# Pico_PSU.net
KiCad netlist of a schematic drawn in Altium Designer
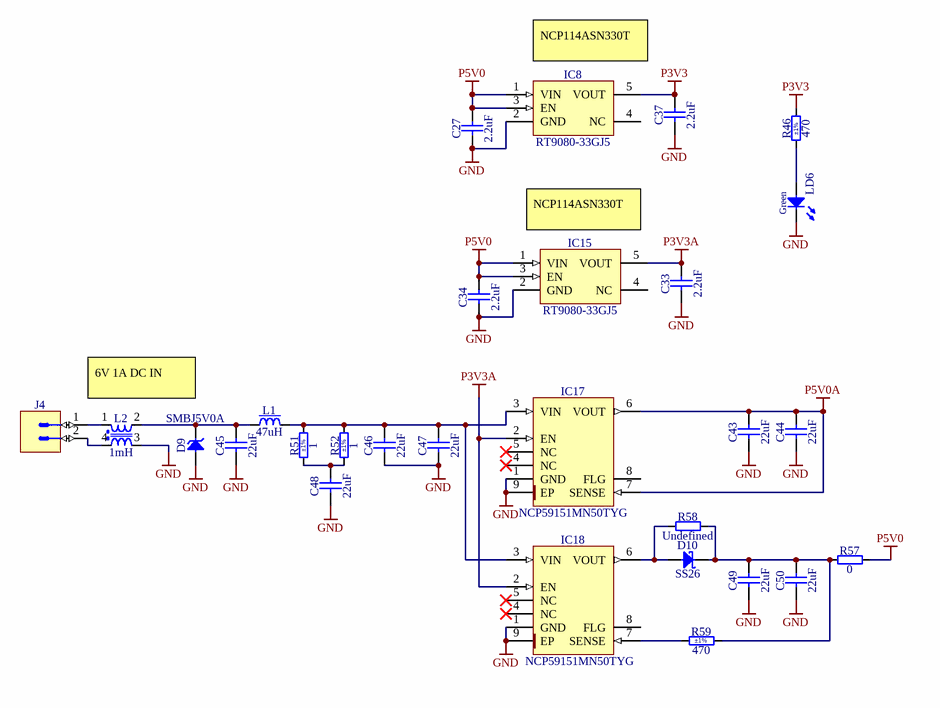
[diagram p0: Pico_PSU.SchDoc]

(export (version "E")
  (design (tool "Eeschema 10.0.6"))
  (components
    (comp (ref "C27")
      (value "2.2uF")
      (footprint "CAPC1608X90N")
      (description "Non-polarised capacitor")
      (fields
        (field (name "PART NUMBER") "CC0603_2.2UF_10V_20%_X7R")
        (field (name "VOLTAGE") "10V")
        (field (name "AUTHOR") "CERN DEM JLC")
      )
      (libsource (lib "Capacitors") (part "Capacitor - non polarized"))
    )
    (comp (ref "C33")
      (value "2.2uF")
      (footprint "CAPC1608X90N")
      (description "Non-polarised capacitor")
      (fields
        (field (name "PART NUMBER") "CC0603_2.2UF_10V_20%_X7R")
        (field (name "VOLTAGE") "10V")
        (field (name "AUTHOR") "CERN DEM JLC")
      )
      (libsource (lib "Capacitors") (part "Capacitor - non polarized"))
    )
    (comp (ref "C34")
      (value "2.2uF")
      (footprint "CAPC1608X90N")
      (description "Non-polarised capacitor")
      (fields
        (field (name "PART NUMBER") "CC0603_2.2UF_10V_20%_X7R")
        (field (name "VOLTAGE") "10V")
        (field (name "AUTHOR") "CERN DEM JLC")
      )
      (libsource (lib "Capacitors") (part "Capacitor - non polarized"))
    )
    (comp (ref "C37")
      (value "2.2uF")
      (footprint "CAPC1608X90N")
      (description "Non-polarised capacitor")
      (fields
        (field (name "PART NUMBER") "CC0603_2.2UF_10V_20%_X7R")
        (field (name "VOLTAGE") "10V")
        (field (name "AUTHOR") "CERN DEM JLC")
      )
      (libsource (lib "Capacitors") (part "Capacitor - non polarized"))
    )
    (comp (ref "C43")
      (value "22uF")
      (footprint "CAPC3216X180N")
      (description "Non-polarised capacitor")
      (fields
        (field (name "PART NUMBER") "CC1206_22UF_10V_10%_X7R")
        (field (name "VOLTAGE") "10V")
        (field (name "AUTHOR") "CERN DEM JLC")
      )
      (libsource (lib "Capacitors") (part "Capacitor - non polarized"))
    )
    (comp (ref "C44")
      (value "22uF")
      (footprint "CAPC3216X180N")
      (description "Non-polarised capacitor")
      (fields
        (field (name "PART NUMBER") "CC1206_22UF_10V_10%_X7R")
        (field (name "VOLTAGE") "10V")
        (field (name "AUTHOR") "CERN DEM JLC")
      )
      (libsource (lib "Capacitors") (part "Capacitor - non polarized"))
    )
    (comp (ref "C45")
      (value "22uF")
      (footprint "CAPC3216X180N")
      (description "Non-polarised capacitor")
      (fields
        (field (name "PART NUMBER") "CC1206_22UF_10V_10%_X7R")
        (field (name "VOLTAGE") "10V")
        (field (name "AUTHOR") "CERN DEM JLC")
      )
      (libsource (lib "Capacitors") (part "Capacitor - non polarized"))
    )
    (comp (ref "C46")
      (value "22uF")
      (footprint "CAPC3216X180N")
      (description "Non-polarised capacitor")
      (fields
        (field (name "PART NUMBER") "CC1206_22UF_10V_10%_X7R")
        (field (name "VOLTAGE") "10V")
        (field (name "AUTHOR") "CERN DEM JLC")
      )
      (libsource (lib "Capacitors") (part "Capacitor - non polarized"))
    )
    (comp (ref "C47")
      (value "22uF")
      (footprint "CAPC3216X180N")
      (description "Non-polarised capacitor")
      (fields
        (field (name "PART NUMBER") "CC1206_22UF_10V_10%_X7R")
        (field (name "VOLTAGE") "10V")
        (field (name "AUTHOR") "CERN DEM JLC")
      )
      (libsource (lib "Capacitors") (part "Capacitor - non polarized"))
    )
    (comp (ref "C48")
      (value "22uF")
      (footprint "CAPC3216X180N")
      (description "Non-polarised capacitor")
      (fields
        (field (name "PART NUMBER") "CC1206_22UF_10V_10%_X7R")
        (field (name "VOLTAGE") "10V")
        (field (name "AUTHOR") "CERN DEM JLC")
      )
      (libsource (lib "Capacitors") (part "Capacitor - non polarized"))
    )
    (comp (ref "C49")
      (value "22uF")
      (footprint "CAPC3216X180N")
      (description "Non-polarised capacitor")
      (fields
        (field (name "PART NUMBER") "CC1206_22UF_10V_10%_X7R")
        (field (name "VOLTAGE") "10V")
        (field (name "AUTHOR") "CERN DEM JLC")
      )
      (libsource (lib "Capacitors") (part "Capacitor - non polarized"))
    )
    (comp (ref "C50")
      (value "22uF")
      (footprint "CAPC3216X180N")
      (description "Non-polarised capacitor")
      (fields
        (field (name "PART NUMBER") "CC1206_22UF_10V_10%_X7R")
        (field (name "VOLTAGE") "10V")
        (field (name "AUTHOR") "CERN DEM JLC")
      )
      (libsource (lib "Capacitors") (part "Capacitor - non polarized"))
    )
    (comp (ref "D9")
      (value "SMBJ5V0A")
      (footprint "DIOM5336X265N")
      (description "Zener Diode")
      (fields
        (field (name "VOLTAGE") "5V")
        (field (name "POWER") "600W")
        (field (name "AUTHOR") "CERN DEM JLC")
      )
      (libsource (lib "ICs And Semiconductors") (part "Diode Zener"))
    )
    (comp (ref "D10")
      (value "SS26")
      (footprint "DIOM5336X265N")
      (description "Schottky Diode")
      (fields
        (field (name "VOLTAGE") "60V")
        (field (name "POWER") "2A")
        (field (name "AUTHOR") "CERN DEM JMW")
      )
      (libsource (lib "ICs And Semiconductors") (part "Diode Schottky"))
    )
    (comp (ref "IC8")
      (value "RT9080-33GJ5")
      (footprint "SOT95P280X100-5N")
      (description "600mA, Low-Dropout Linear Regulator")
      (fields (field (name "MANUFACTURER") "RICHTEK") (field (name "AUTHOR") "CERN DEM BC"))
      (libsource (lib "ICs And Semiconductors") (part "RT9080-J5"))
    )
    (comp (ref "IC15")
      (value "RT9080-33GJ5")
      (footprint "SOT95P280X100-5N")
      (description "600mA, Low-Dropout Linear Regulator")
      (fields (field (name "MANUFACTURER") "RICHTEK") (field (name "AUTHOR") "CERN DEM BC"))
      (libsource (lib "ICs And Semiconductors") (part "RT9080-J5"))
    )
    (comp (ref "IC17")
      (value "NCP59151MN50TYG")
      (footprint "SON80P400X400X100-9N-R221X239")
      (description "1.5 A, Very Low-Dropout (VLDO) Fast Transient Response Regulator")
      (fields
        (field (name "MANUFACTURER") "ON SEMICONDUCTOR")
        (field (name "MANUFACTURER PART NUMBER") "NCP59151MN50TY")
        (field (name "AUTHOR") "CERN DEM JLC")
      )
      (libsource (lib "ICs And Semiconductors") (part "NCP59151MN"))
    )
    (comp (ref "IC18")
      (value "NCP59151MN50TYG")
      (footprint "SON80P400X400X100-9N-R221X239")
      (description "1.5 A, Very Low-Dropout (VLDO) Fast Transient Response Regulator")
      (fields
        (field (name "MANUFACTURER") "ON SEMICONDUCTOR")
        (field (name "MANUFACTURER PART NUMBER") "NCP59151MN50TY")
        (field (name "AUTHOR") "CERN DEM JLC")
      )
      (libsource (lib "ICs And Semiconductors") (part "NCP59151MN"))
    )
    (comp (ref "J4")
      (value "~")
      (footprint "PHOENIX_1803277")
      (description "Connector 2 Male")
      (fields
        (field (name "PART NUMBER") "PHOENIX_1803277")
        (field (name "MANUFACTURER") "PHOENIX CONTACT")
        (field (name "AUTHOR") "CERN DEM JLC")
      )
      (libsource (lib "Connectors") (part "Connector 2 Male"))
    )
    (comp (ref "L1")
      (value "47uH")
      (footprint "IND_WURTH_WE-LHMI_7050")
      (description "Inductor With Core")
      (fields
        (field (name "PART NUMBER") "IND_47UH_20%_WURTH_WE-LHMI_74437349470")
        (field (name "POWER") "1.45A")
        (field (name "AUTHOR") "CERN DEM HF")
      )
      (libsource (lib "Inductors & Transformers") (part "Inductor With Magnetic core"))
    )
    (comp (ref "L2")
      (value "1mH")
      (footprint "IND_BOURNS_SRF1006")
      (description "Inductor Common Mode")
      (fields
        (field (name "PART NUMBER") "IND_1MH_40%_BOURNS_SRF1006")
        (field (name "POWER") "0.95A")
        (field (name "AUTHOR") "CERN DEM HF")
      )
      (libsource (lib "Inductors & Transformers") (part "Inductor Common Mode 1Dot-2 4Dot-3"))
    )
    (comp (ref "LD6")
      (value "Green")
      (footprint "LED_AVAGO_HSME-C110")
      (description "LED Green 1C 2A")
      (fields
        (field (name "PART NUMBER") "LED_AVAGO_HSME-C110")
        (field (name "MANUFACTURER") "AVAGO TECHNOLOGIES")
        (field (name "AUTHOR") "CERN DEM JMW")
      )
      (libsource (lib "ICs And Semiconductors") (part "LED Green 1C 2A"))
    )
    (comp (ref "R46")
      (value "470")
      (footprint "RESC1608X55N")
      (description "Resistor - 1%")
      (fields
        (field (name "TOLERANCE") "±1%")
        (field (name "PART NUMBER") "R0603_470R_1%_0.1W_100PPM")
        (field (name "POWER") "0.1W")
        (field (name "AUTHOR") "CERN DEM JLC")
      )
      (libsource (lib "Resistors") (part "Resistor - 1%"))
    )
    (comp (ref "R51")
      (value "1")
      (footprint "RESC1608X55N")
      (description "Resistor - 1%")
      (fields
        (field (name "TOLERANCE") "±1%")
        (field (name "PART NUMBER") "R0603_1R_1%_0.1W_200PPM")
        (field (name "POWER") "0.1W")
        (field (name "AUTHOR") "CERN DEM JLC")
      )
      (libsource (lib "Resistors") (part "Resistor - 1%"))
    )
    (comp (ref "R52")
      (value "1")
      (footprint "RESC1608X55N")
      (description "Resistor - 1%")
      (fields
        (field (name "TOLERANCE") "±1%")
        (field (name "PART NUMBER") "R0603_1R_1%_0.1W_200PPM")
        (field (name "POWER") "0.1W")
        (field (name "AUTHOR") "CERN DEM JLC")
      )
      (libsource (lib "Resistors") (part "Resistor - 1%"))
    )
    (comp (ref "R57")
      (value "0")
      (footprint "RESC1608X55N")
      (description "Resistor")
      (fields
        (field (name "PART NUMBER") "R0603_0R_JUMPER")
        (field (name "MANUFACTURER") "GENERIC")
        (field (name "AUTHOR") "CERN DEM JLC")
      )
      (libsource (lib "Resistors") (part "Resistor"))
    )
    (comp (ref "R58")
      (value "Undefined")
      (footprint "RESC1608X55N")
      (description "Resistor")
      (fields (field (name "PART NUMBER") "R0603_NO-VALUE") (field (name "AUTHOR") "CERN DEM JLC"))
      (libsource (lib "Resistors") (part "Resistor"))
    )
    (comp (ref "R59")
      (value "470")
      (footprint "RESC1608X55N")
      (description "Resistor - 1%")
      (fields
        (field (name "TOLERANCE") "±1%")
        (field (name "PART NUMBER") "R0603_470R_1%_0.1W_100PPM")
        (field (name "POWER") "0.1W")
        (field (name "AUTHOR") "CERN DEM JLC")
      )
      (libsource (lib "Resistors") (part "Resistor - 1%"))
    )
  )
  (nets
    (net (code "1") (name "GND") (class "Default")
      (node (ref "C27") (pin "1") (pinfunction "1_1") (pintype "passive"))
      (node (ref "C33") (pin "1") (pinfunction "1_1") (pintype "passive"))
      (node (ref "C34") (pin "1") (pinfunction "1_1") (pintype "passive"))
      (node (ref "C37") (pin "1") (pinfunction "1_1") (pintype "passive"))
      (node (ref "C43") (pin "1") (pinfunction "1_1") (pintype "passive"))
      (node (ref "C44") (pin "1") (pinfunction "1_1") (pintype "passive"))
      (node (ref "C45") (pin "1") (pinfunction "1_1") (pintype "passive"))
      (node (ref "C46") (pin "1") (pinfunction "1_1") (pintype "passive"))
      (node (ref "C47") (pin "1") (pinfunction "1_1") (pintype "passive"))
      (node (ref "C48") (pin "1") (pinfunction "1_1") (pintype "passive"))
      (node (ref "C49") (pin "1") (pinfunction "1_1") (pintype "passive"))
      (node (ref "C50") (pin "1") (pinfunction "1_1") (pintype "passive"))
      (node (ref "D9") (pin "2") (pinfunction "A_2") (pintype "passive"))
      (node (ref "IC15") (pin "2") (pinfunction "GND_2") (pintype "power_in"))
      (node (ref "IC17") (pin "1") (pinfunction "GND_1") (pintype "power_in"))
      (node (ref "IC17") (pin "9") (pinfunction "EP_9") (pintype "power_in"))
      (node (ref "IC18") (pin "1") (pinfunction "GND_1") (pintype "power_in"))
      (node (ref "IC18") (pin "9") (pinfunction "EP_9") (pintype "power_in"))
      (node (ref "IC8") (pin "2") (pinfunction "GND_2") (pintype "power_in"))
      (node (ref "L2") (pin "3") (pinfunction "3_3") (pintype "passive"))
      (node (ref "LD6") (pin "1") (pinfunction "C_1") (pintype "passive"))
    )
    (net (code "2") (name "Net-(C48-Pad2)") (class "Default")
      (node (ref "C48") (pin "2") (pinfunction "2_2") (pintype "passive"))
      (node (ref "R51") (pin "1") (pinfunction "1_1") (pintype "passive"))
      (node (ref "R52") (pin "1") (pinfunction "1_1") (pintype "passive"))
    )
    (net (code "3") (name "Net-(D9-C)") (class "Default")
      (node (ref "C45") (pin "2") (pinfunction "2_2") (pintype "passive"))
      (node (ref "D9") (pin "1") (pinfunction "C_1") (pintype "passive"))
      (node (ref "L1") (pin "1") (pinfunction "1_1") (pintype "passive"))
      (node (ref "L2") (pin "2") (pinfunction "2_2") (pintype "passive"))
    )
    (net (code "4") (name "Net-(D10-A)") (class "Default")
      (node (ref "D10") (pin "2") (pinfunction "A_2") (pintype "passive"))
      (node (ref "IC18") (pin "6") (pinfunction "VOUT_6") (pintype "output"))
      (node (ref "R58") (pin "1") (pinfunction "1_1") (pintype "passive"))
    )
    (net (code "5") (name "Net-(D10-C)") (class "Default")
      (node (ref "C49") (pin "2") (pinfunction "2_2") (pintype "passive"))
      (node (ref "C50") (pin "2") (pinfunction "2_2") (pintype "passive"))
      (node (ref "D10") (pin "1") (pinfunction "C_1") (pintype "passive"))
      (node (ref "R57") (pin "1") (pinfunction "1_1") (pintype "passive"))
      (node (ref "R58") (pin "2") (pinfunction "2_2") (pintype "passive"))
      (node (ref "R59") (pin "2") (pinfunction "2_2") (pintype "passive"))
    )
    (net (code "6") (name "Net-(IC17-VIN)") (class "Default")
      (node (ref "C46") (pin "2") (pinfunction "2_2") (pintype "passive"))
      (node (ref "C47") (pin "2") (pinfunction "2_2") (pintype "passive"))
      (node (ref "IC17") (pin "3") (pinfunction "VIN_3") (pintype "input"))
      (node (ref "IC18") (pin "3") (pinfunction "VIN_3") (pintype "input"))
      (node (ref "L1") (pin "2") (pinfunction "2_2") (pintype "passive"))
      (node (ref "R51") (pin "2") (pinfunction "2_2") (pintype "passive"))
      (node (ref "R52") (pin "2") (pinfunction "2_2") (pintype "passive"))
    )
    (net (code "7") (name "Net-(IC18-SENSE)") (class "Default")
      (node (ref "IC18") (pin "7") (pinfunction "SENSE_7") (pintype "input"))
      (node (ref "R59") (pin "1") (pinfunction "1_1") (pintype "passive"))
    )
    (net (code "8") (name "Net-(J4-Pad1)") (class "Default")
      (node (ref "J4") (pin "1") (pinfunction "1_1") (pintype "bidirectional"))
      (node (ref "L2") (pin "1") (pinfunction "1_1") (pintype "passive"))
    )
    (net (code "9") (name "Net-(J4-Pad2)") (class "Default")
      (node (ref "J4") (pin "2") (pinfunction "2_2") (pintype "bidirectional"))
      (node (ref "L2") (pin "4") (pinfunction "4_4") (pintype "passive"))
    )
    (net (code "10") (name "Net-(LD6-A)") (class "Default")
      (node (ref "LD6") (pin "2") (pinfunction "A_2") (pintype "passive"))
      (node (ref "R46") (pin "1") (pinfunction "1_1") (pintype "passive"))
    )
    (net (code "11") (name "P3V3") (class "Default")
      (node (ref "C37") (pin "2") (pinfunction "2_2") (pintype "passive"))
      (node (ref "IC8") (pin "5") (pinfunction "VOUT_5") (pintype "power_in"))
      (node (ref "R46") (pin "2") (pinfunction "2_2") (pintype "passive"))
    )
    (net (code "12") (name "P3V3A") (class "Default")
      (node (ref "C33") (pin "2") (pinfunction "2_2") (pintype "passive"))
      (node (ref "IC15") (pin "5") (pinfunction "VOUT_5") (pintype "power_in"))
      (node (ref "IC17") (pin "2") (pinfunction "EN_2") (pintype "input"))
      (node (ref "IC18") (pin "2") (pinfunction "EN_2") (pintype "input"))
    )
    (net (code "13") (name "P5V0") (class "Default")
      (node (ref "C27") (pin "2") (pinfunction "2_2") (pintype "passive"))
      (node (ref "C34") (pin "2") (pinfunction "2_2") (pintype "passive"))
      (node (ref "IC15") (pin "1") (pinfunction "VIN_1") (pintype "input"))
      (node (ref "IC15") (pin "3") (pinfunction "EN_3") (pintype "input"))
      (node (ref "IC8") (pin "1") (pinfunction "VIN_1") (pintype "input"))
      (node (ref "IC8") (pin "3") (pinfunction "EN_3") (pintype "input"))
      (node (ref "R57") (pin "2") (pinfunction "2_2") (pintype "passive"))
    )
    (net (code "14") (name "P5V0A") (class "Default")
      (node (ref "C43") (pin "2") (pinfunction "2_2") (pintype "passive"))
      (node (ref "C44") (pin "2") (pinfunction "2_2") (pintype "passive"))
      (node (ref "IC17") (pin "6") (pinfunction "VOUT_6") (pintype "output"))
      (node (ref "IC17") (pin "7") (pinfunction "SENSE_7") (pintype "input"))
    )
    (net (code "15") (name "unconnected-(IC8-NC-Pad4)") (class "Default")
      (node (ref "IC8") (pin "4") (pinfunction "NC_4") (pintype "passive"))
    )
    (net (code "16") (name "unconnected-(IC15-NC-Pad4)") (class "Default")
      (node (ref "IC15") (pin "4") (pinfunction "NC_4") (pintype "passive"))
    )
    (net (code "17") (name "unconnected-(IC17-FLG-Pad8)") (class "Default")
      (node (ref "IC17") (pin "8") (pinfunction "FLG_8") (pintype "open_collector"))
    )
    (net (code "18") (name "unconnected-(IC17-NC-Pad4)") (class "Default")
      (node (ref "IC17") (pin "4") (pinfunction "NC_4") (pintype "passive+no_connect"))
    )
    (net (code "19") (name "unconnected-(IC17-NC-Pad5)") (class "Default")
      (node (ref "IC17") (pin "5") (pinfunction "NC_5") (pintype "passive+no_connect"))
    )
    (net (code "20") (name "unconnected-(IC18-FLG-Pad8)") (class "Default")
      (node (ref "IC18") (pin "8") (pinfunction "FLG_8") (pintype "open_collector"))
    )
    (net (code "21") (name "unconnected-(IC18-NC-Pad4)") (class "Default")
      (node (ref "IC18") (pin "4") (pinfunction "NC_4") (pintype "passive+no_connect"))
    )
    (net (code "22") (name "unconnected-(IC18-NC-Pad5)") (class "Default")
      (node (ref "IC18") (pin "5") (pinfunction "NC_5") (pintype "passive+no_connect"))
    )
  )
)
